# 12T_FULL_BRIDGE.net
KiCad netlist of a schematic drawn in EAGLE
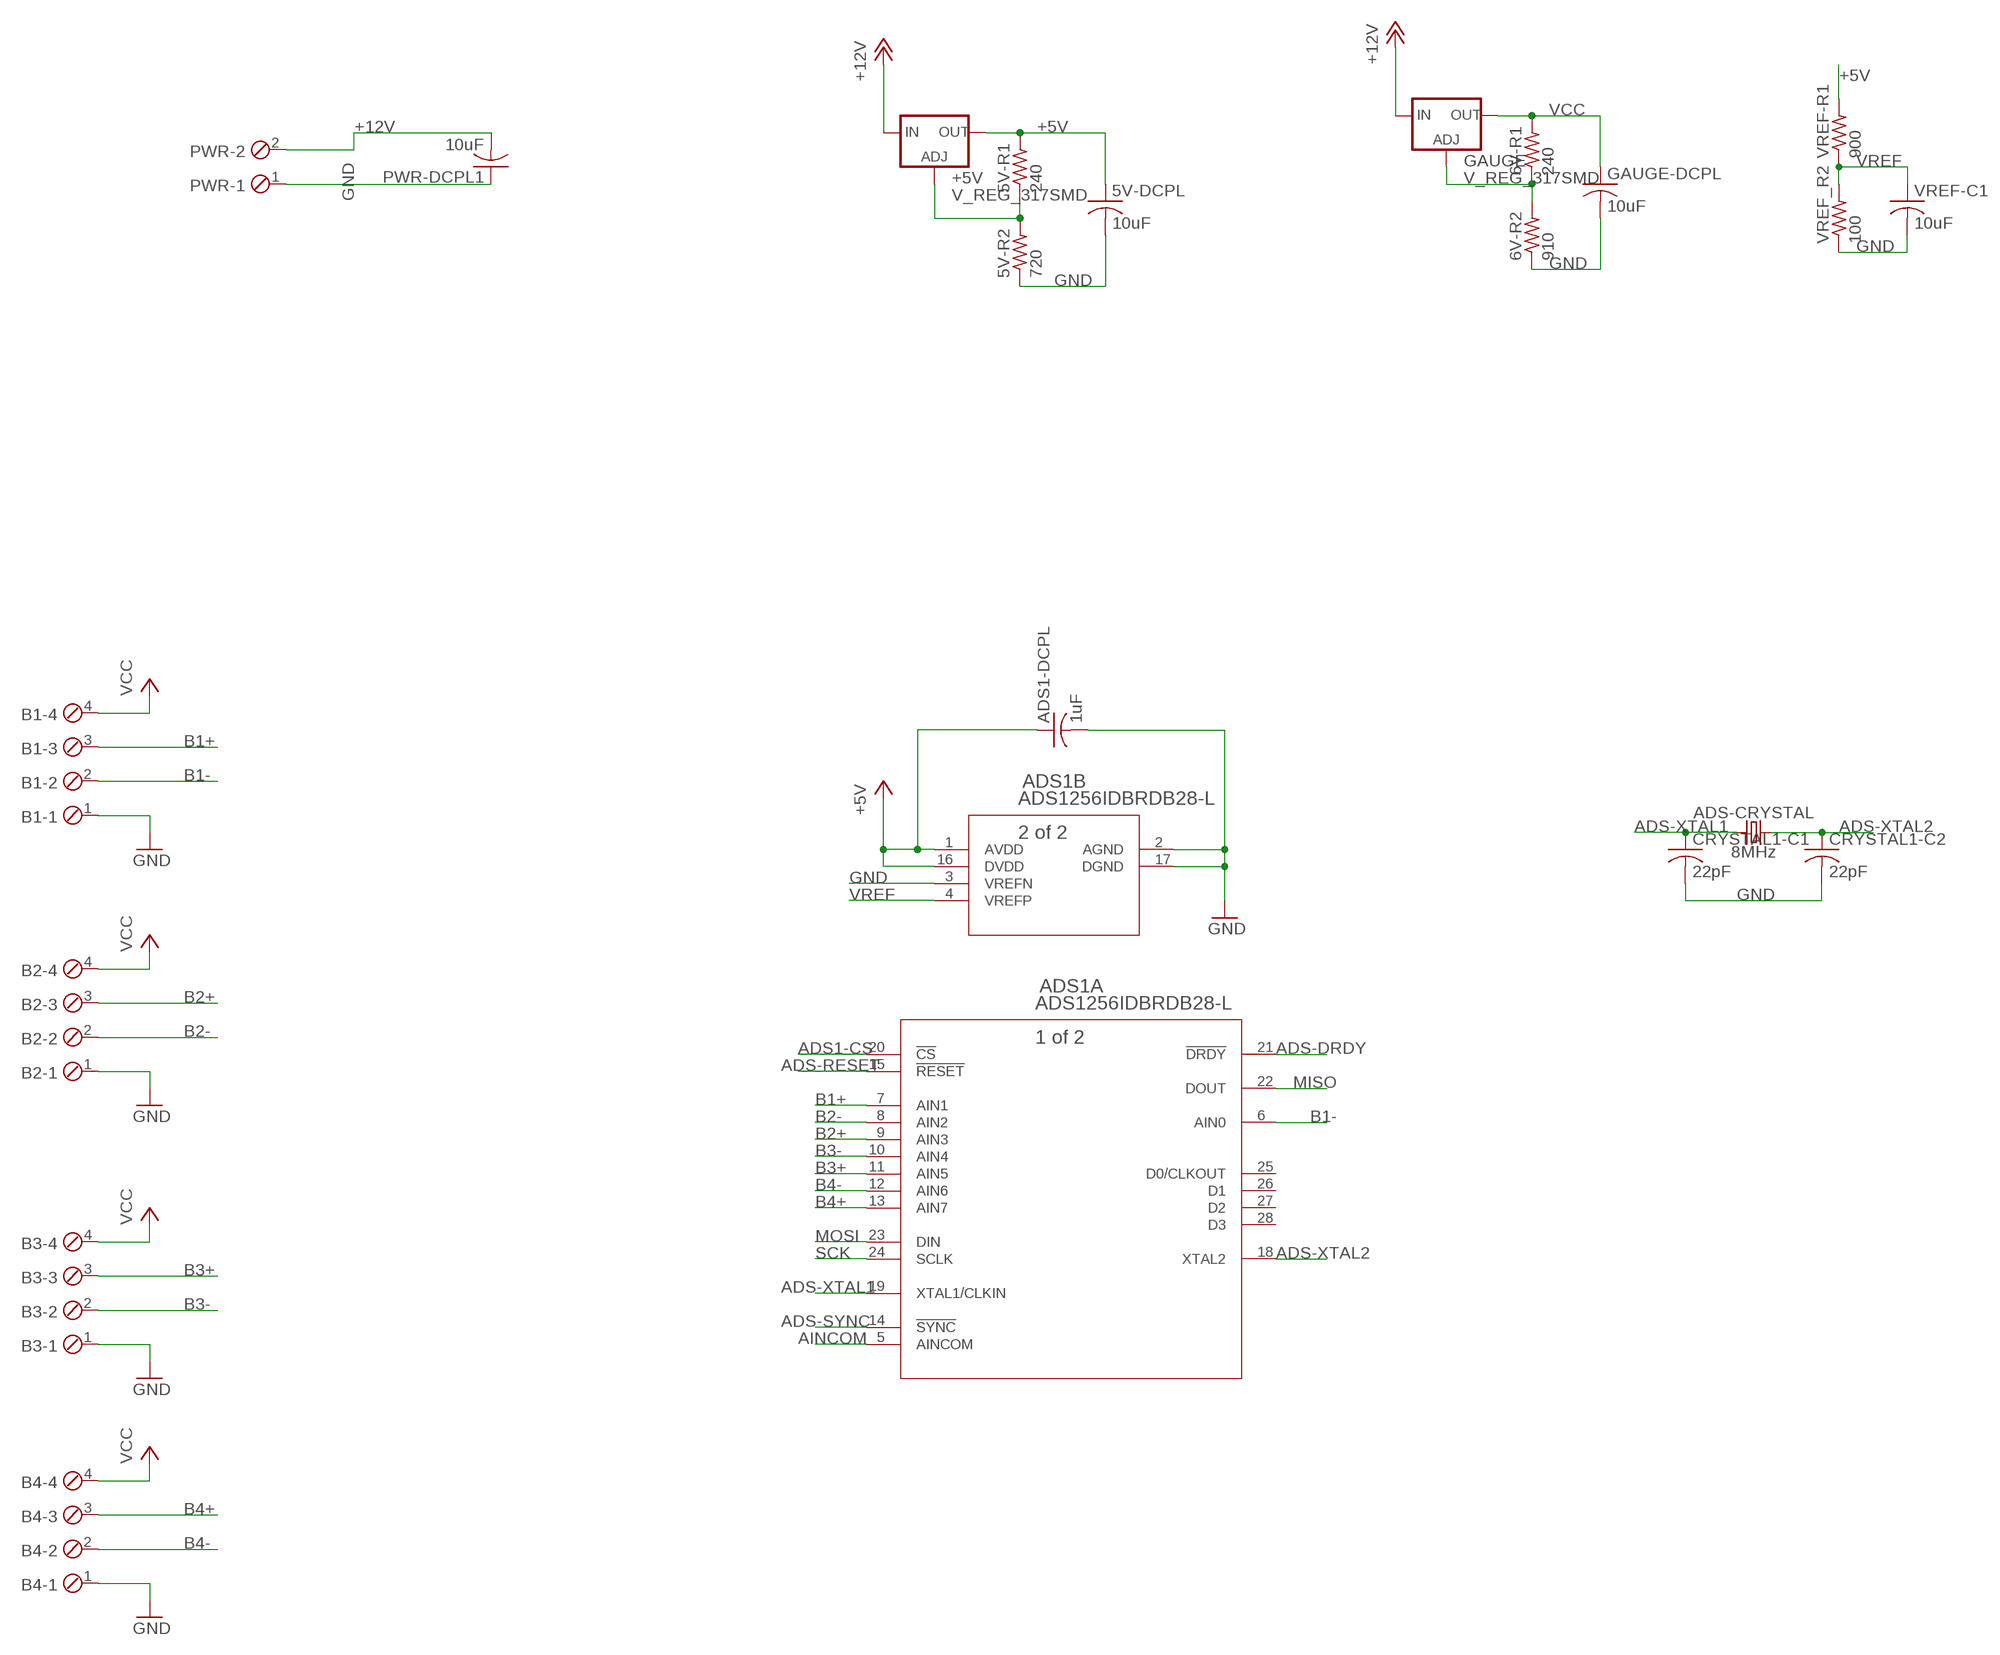
[diagram p0: schematic, sheet 1, part 1 of 2]
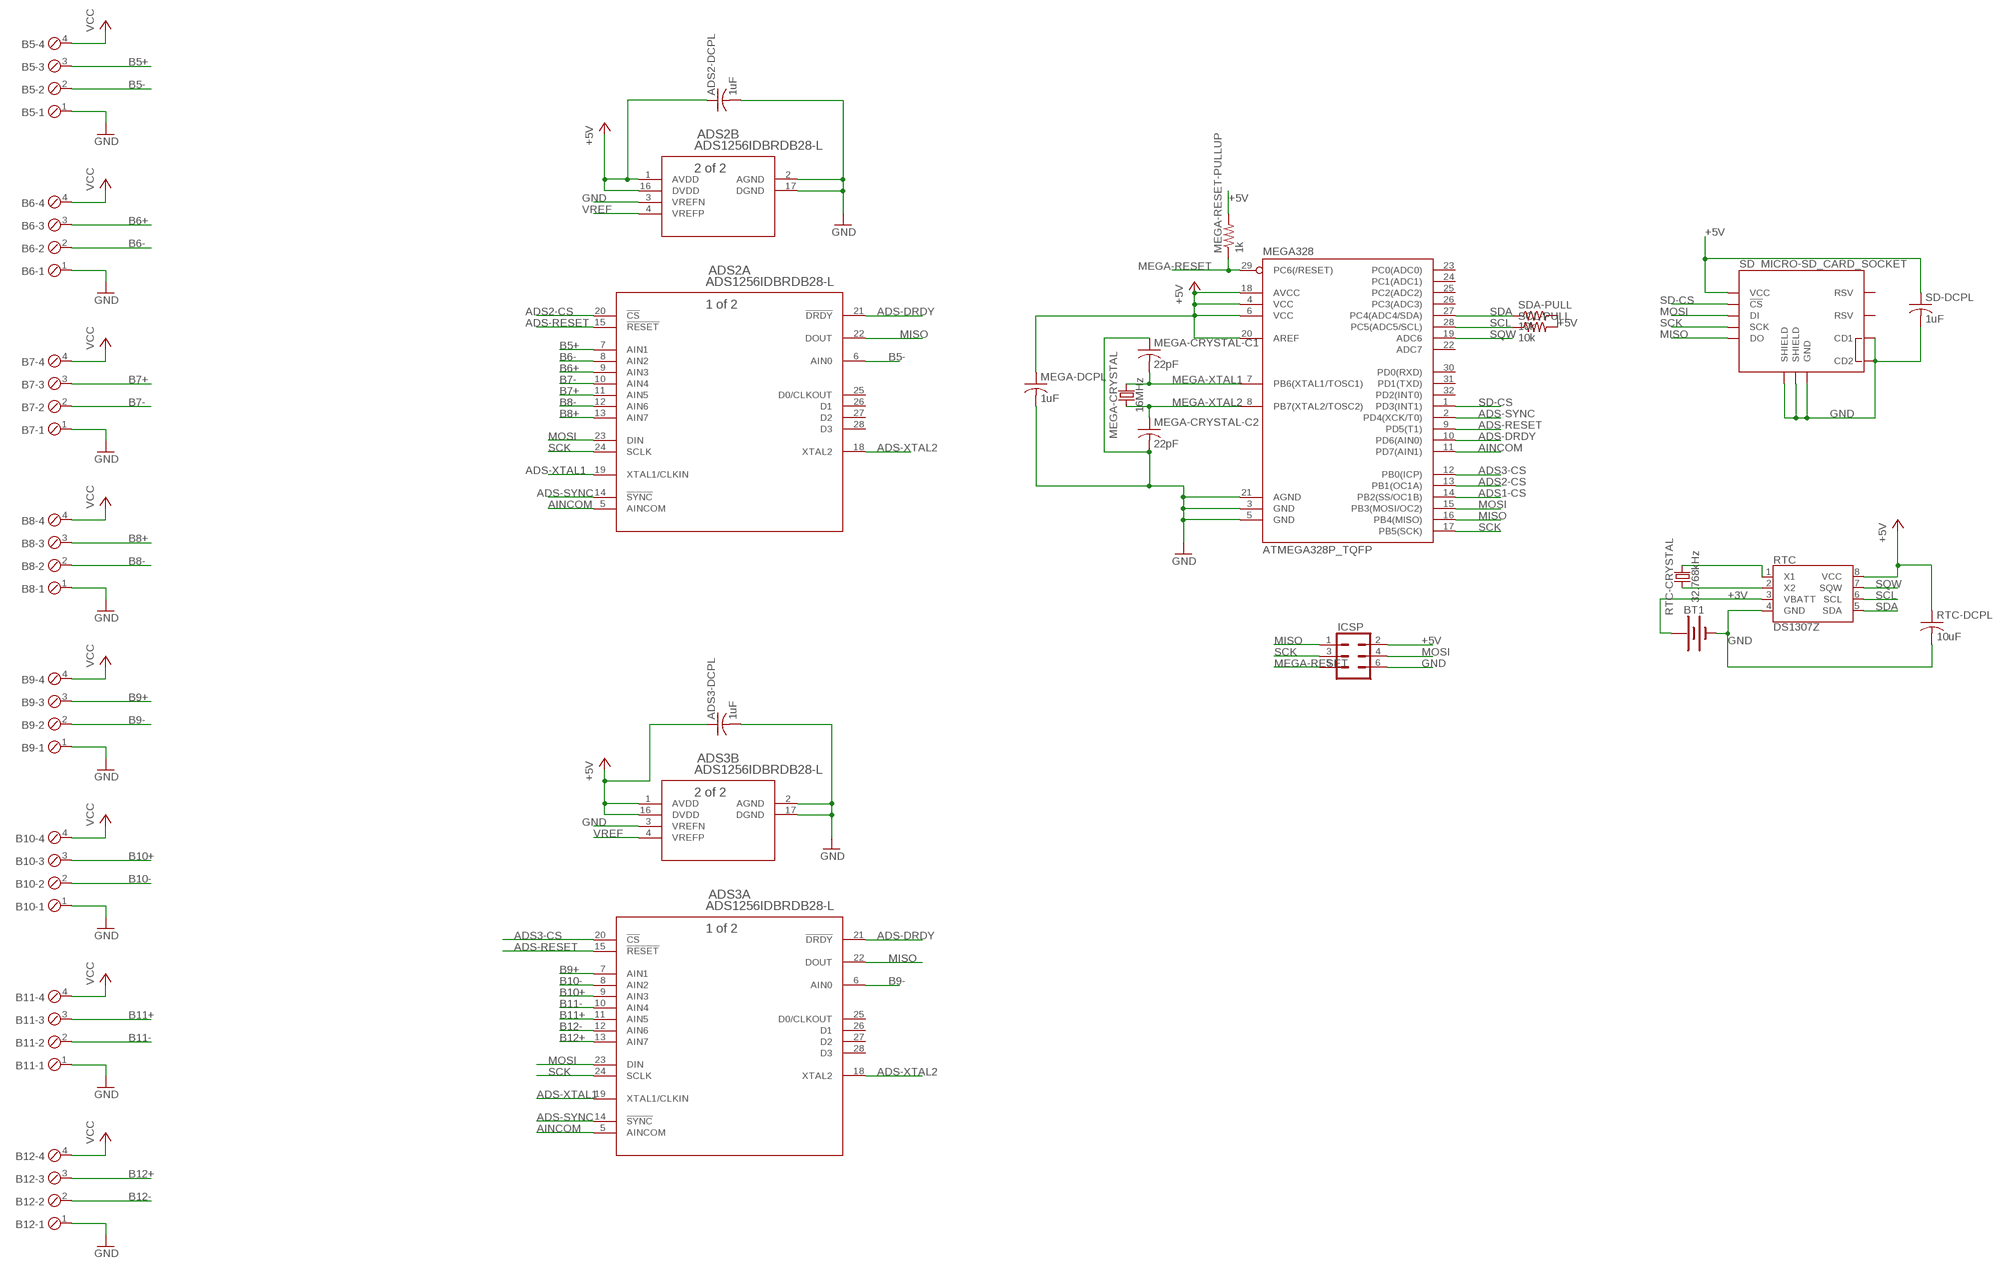
[diagram p1: schematic, sheet 1, part 2 of 2]

(export (version "E")
  (design (tool "Eeschema 10.0.6"))
  (components
    (comp (ref "+5V")
      (value "V_REG_317SMD")
      (footprint "eagle-import:SOT223")
      (libsource (lib "eagle-import") (part "V_REG_317SMD"))
    )
    (comp (ref "5V-DCPL")
      (value "10uF")
      (footprint "eagle-import:C1206")
      (libsource (lib "eagle-import") (part "C-USC1206"))
    )
    (comp (ref "5V-R1")
      (value "240")
      (footprint "eagle-import:R1206")
      (libsource (lib "eagle-import") (part "R-US_R1206"))
    )
    (comp (ref "5V-R2")
      (value "720")
      (footprint "eagle-import:R1206")
      (libsource (lib "eagle-import") (part "R-US_R1206"))
    )
    (comp (ref "6V-R1")
      (value "240")
      (footprint "eagle-import:R1206")
      (libsource (lib "eagle-import") (part "R-US_R1206"))
    )
    (comp (ref "6V-R2")
      (value "910")
      (footprint "eagle-import:R1206")
      (libsource (lib "eagle-import") (part "R-US_R1206"))
    )
    (comp (ref "ADS-CRYSTAL")
      (value "8MHz")
      (footprint "eagle-import:CRYSTAL-SMD-5X3.2-4PAD")
      (libsource (lib "eagle-import") (part "CRYSTAL-8MHZSMD-5X3.2"))
    )
    (comp (ref "ADS1")
      (value "ADS1256IDBRDB28-L")
      (footprint "eagle-import:DB28-L")
      (fields (field (name "MANUFACTURER_PART_NUMBER") "ADS1256IDBR"))
      (libsource (lib "eagle-import") (part "ADS1256IDBRDB28-L"))
    )
    (comp (ref "ADS1-DCPL")
      (value "1uF")
      (footprint "eagle-import:C1206K")
      (libsource (lib "eagle-import") (part "C-USC1206K"))
    )
    (comp (ref "ADS2")
      (value "ADS1256IDBRDB28-L")
      (footprint "eagle-import:DB28-L")
      (fields (field (name "MANUFACTURER_PART_NUMBER") "ADS1256IDBR"))
      (libsource (lib "eagle-import") (part "ADS1256IDBRDB28-L"))
    )
    (comp (ref "ADS2-DCPL")
      (value "1uF")
      (footprint "eagle-import:C1206K")
      (libsource (lib "eagle-import") (part "C-USC1206K"))
    )
    (comp (ref "ADS3")
      (value "ADS1256IDBRDB28-L")
      (footprint "eagle-import:DB28-L")
      (fields (field (name "MANUFACTURER_PART_NUMBER") "ADS1256IDBR"))
      (libsource (lib "eagle-import") (part "ADS1256IDBRDB28-L"))
    )
    (comp (ref "ADS3-DCPL")
      (value "1uF")
      (footprint "eagle-import:C1206K")
      (libsource (lib "eagle-import") (part "C-USC1206K"))
    )
    (comp (ref "B1")
      (value "MPT4")
      (footprint "eagle-import:4POL254")
      (libsource (lib "eagle-import") (part "MPT4"))
    )
    (comp (ref "B2")
      (value "MPT4")
      (footprint "eagle-import:4POL254")
      (libsource (lib "eagle-import") (part "MPT4"))
    )
    (comp (ref "B3")
      (value "MPT4")
      (footprint "eagle-import:4POL254")
      (libsource (lib "eagle-import") (part "MPT4"))
    )
    (comp (ref "B4")
      (value "MPT4")
      (footprint "eagle-import:4POL254")
      (libsource (lib "eagle-import") (part "MPT4"))
    )
    (comp (ref "B5")
      (value "MPT4")
      (footprint "eagle-import:4POL254")
      (libsource (lib "eagle-import") (part "MPT4"))
    )
    (comp (ref "B6")
      (value "MPT4")
      (footprint "eagle-import:4POL254")
      (libsource (lib "eagle-import") (part "MPT4"))
    )
    (comp (ref "B7")
      (value "MPT4")
      (footprint "eagle-import:4POL254")
      (libsource (lib "eagle-import") (part "MPT4"))
    )
    (comp (ref "B8")
      (value "MPT4")
      (footprint "eagle-import:4POL254")
      (libsource (lib "eagle-import") (part "MPT4"))
    )
    (comp (ref "B9")
      (value "MPT4")
      (footprint "eagle-import:4POL254")
      (libsource (lib "eagle-import") (part "MPT4"))
    )
    (comp (ref "B10")
      (value "MPT4")
      (footprint "eagle-import:4POL254")
      (libsource (lib "eagle-import") (part "MPT4"))
    )
    (comp (ref "B11")
      (value "MPT4")
      (footprint "eagle-import:4POL254")
      (libsource (lib "eagle-import") (part "MPT4"))
    )
    (comp (ref "B12")
      (value "MPT4")
      (footprint "eagle-import:4POL254")
      (libsource (lib "eagle-import") (part "MPT4"))
    )
    (comp (ref "BT1")
      (value "BATTERY-12MM_SMD")
      (footprint "eagle-import:BATTCON_12MM")
      (libsource (lib "eagle-import") (part "BATTERY-12MM_SMD"))
    )
    (comp (ref "CRYSTAL1-C1")
      (value "22pF")
      (footprint "eagle-import:C1206")
      (libsource (lib "eagle-import") (part "C-USC1206"))
    )
    (comp (ref "CRYSTAL1-C2")
      (value "22pF")
      (footprint "eagle-import:C1206")
      (libsource (lib "eagle-import") (part "C-USC1206"))
    )
    (comp (ref "GAUGE")
      (value "V_REG_317SMD")
      (footprint "eagle-import:SOT223")
      (libsource (lib "eagle-import") (part "V_REG_317SMD"))
    )
    (comp (ref "GAUGE-DCPL")
      (value "10uF")
      (footprint "eagle-import:C1206")
      (libsource (lib "eagle-import") (part "C-USC1206"))
    )
    (comp (ref "ICSP")
      (value "CONN_03X2FEMALE_SMD")
      (footprint "eagle-import:2X3_SMD")
      (libsource (lib "eagle-import") (part "CONN_03X2FEMALE_SMD"))
    )
    (comp (ref "MEGA-CRYSTAL")
      (value "16MHz")
      (footprint "eagle-import:CRYSTAL-SMD-5X3.2-4PAD")
      (libsource (lib "eagle-import") (part "CRYSTAL-16MHZSMD-5X3.2"))
    )
    (comp (ref "MEGA-CRYSTAL-C1")
      (value "22pF")
      (footprint "eagle-import:C1206K")
      (libsource (lib "eagle-import") (part "C-USC1206K"))
    )
    (comp (ref "MEGA-CRYSTAL-C2")
      (value "22pF")
      (footprint "eagle-import:C1206K")
      (libsource (lib "eagle-import") (part "C-USC1206K"))
    )
    (comp (ref "MEGA-DCPL")
      (value "1uF")
      (footprint "eagle-import:C1206K")
      (libsource (lib "eagle-import") (part "C-USC1206K"))
    )
    (comp (ref "MEGA-RESET-PULLUP")
      (value "1k")
      (footprint "eagle-import:R1206")
      (libsource (lib "eagle-import") (part "R-US_R1206"))
    )
    (comp (ref "MEGA328")
      (value "ATMEGA328P_TQFP")
      (footprint "eagle-import:TQFP32-08")
      (libsource (lib "eagle-import") (part "ATMEGA328P_TQFP"))
    )
    (comp (ref "PWR")
      (value "MPT2")
      (footprint "eagle-import:2POL254")
      (libsource (lib "eagle-import") (part "MPT2"))
    )
    (comp (ref "PWR-DCPL1")
      (value "10uF")
      (footprint "eagle-import:C1206")
      (libsource (lib "eagle-import") (part "C-USC1206"))
    )
    (comp (ref "RTC")
      (value "DS1307Z")
      (footprint "eagle-import:SO08-0.15")
      (libsource (lib "eagle-import") (part "DS1307Z"))
    )
    (comp (ref "RTC-CRYSTAL")
      (value "32.768kHz")
      (footprint "eagle-import:CRYSTAL-SMD-3.2X1.5MM")
      (libsource (lib "eagle-import") (part "CRYSTAL-32.768KHZSMD-3.2X1.5"))
    )
    (comp (ref "RTC-DCPL")
      (value "10uF")
      (footprint "eagle-import:C1206")
      (libsource (lib "eagle-import") (part "C-USC1206"))
    )
    (comp (ref "SCL-PULL")
      (value "10k")
      (footprint "eagle-import:R1206")
      (libsource (lib "eagle-import") (part "resistor_348_R-US_R1206"))
    )
    (comp (ref "SD")
      (value "MICRO-SD_CARD_SOCKET")
      (footprint "eagle-import:MICRO-SD-SOCKET")
      (libsource (lib "eagle-import") (part "MICRO-SD_CARD_SOCKET"))
    )
    (comp (ref "SD-DCPL")
      (value "1uF")
      (footprint "eagle-import:C1206K")
      (libsource (lib "eagle-import") (part "resistor_348_C-USC1206K"))
    )
    (comp (ref "SDA-PULL")
      (value "10k")
      (footprint "eagle-import:R1206")
      (libsource (lib "eagle-import") (part "resistor_348_R-US_R1206"))
    )
    (comp (ref "VREF-C1")
      (value "10uF")
      (footprint "eagle-import:C1206")
      (libsource (lib "eagle-import") (part "C-USC1206"))
    )
    (comp (ref "VREF-R1")
      (value "900")
      (footprint "eagle-import:R1206")
      (libsource (lib "eagle-import") (part "R-US_R1206"))
    )
    (comp (ref "VREF_R2")
      (value "100")
      (footprint "eagle-import:R1206")
      (libsource (lib "eagle-import") (part "R-US_R1206"))
    )
  )
  (nets
    (net (code "1") (name "+5V") (class "Default")
      (node (ref "+5V") (pin "2") (pinfunction "OUT_2") (pintype "output"))
      (node (ref "5V-DCPL") (pin "1") (pinfunction "1_1") (pintype "passive"))
      (node (ref "5V-R1") (pin "2") (pinfunction "2_2") (pintype "passive"))
      (node (ref "ADS1") (pin "1") (pinfunction "AVDD_1") (pintype "passive"))
      (node (ref "ADS1") (pin "16") (pinfunction "DVDD_16") (pintype "power_in"))
      (node (ref "ADS1-DCPL") (pin "1") (pinfunction "1_1") (pintype "passive"))
      (node (ref "ADS2") (pin "1") (pinfunction "AVDD_1") (pintype "passive"))
      (node (ref "ADS2") (pin "16") (pinfunction "DVDD_16") (pintype "power_in"))
      (node (ref "ADS2-DCPL") (pin "1") (pinfunction "1_1") (pintype "passive"))
      (node (ref "ADS3") (pin "1") (pinfunction "AVDD_1") (pintype "passive"))
      (node (ref "ADS3") (pin "16") (pinfunction "DVDD_16") (pintype "power_in"))
      (node (ref "ADS3-DCPL") (pin "1") (pinfunction "1_1") (pintype "passive"))
      (node (ref "ICSP") (pin "2") (pinfunction "2_2") (pintype "bidirectional"))
      (node (ref "MEGA-DCPL") (pin "1") (pinfunction "1_1") (pintype "passive"))
      (node (ref "MEGA-RESET-PULLUP") (pin "2") (pinfunction "2_2") (pintype "passive"))
      (node (ref "MEGA328") (pin "18") (pinfunction "AVCC_18") (pintype "bidirectional"))
      (node (ref "MEGA328") (pin "20") (pinfunction "AREF_20") (pintype "bidirectional"))
      (node (ref "MEGA328") (pin "4") (pinfunction "VCC_4") (pintype "bidirectional"))
      (node (ref "MEGA328") (pin "6") (pinfunction "VCC_6") (pintype "bidirectional"))
      (node (ref "RTC") (pin "8") (pinfunction "VCC_8") (pintype "bidirectional"))
      (node (ref "RTC-DCPL") (pin "1") (pinfunction "1_1") (pintype "passive"))
      (node (ref "SCL-PULL") (pin "2") (pinfunction "2_2") (pintype "passive"))
      (node (ref "SD") (pin "VCC") (pinfunction "VCC_VCC") (pintype "bidirectional"))
      (node (ref "SD-DCPL") (pin "1") (pinfunction "1_1") (pintype "passive"))
      (node (ref "SDA-PULL") (pin "2") (pinfunction "2_2") (pintype "passive"))
      (node (ref "VREF-R1") (pin "2") (pinfunction "2_2") (pintype "passive"))
    )
    (net (code "2") (name "+12V") (class "Default")
      (node (ref "+5V") (pin "3") (pinfunction "IN_3") (pintype "input"))
      (node (ref "GAUGE") (pin "3") (pinfunction "IN_3") (pintype "input"))
      (node (ref "PWR") (pin "2") (pinfunction "1_2") (pintype "passive"))
      (node (ref "PWR-DCPL1") (pin "2") (pinfunction "2_2") (pintype "passive"))
    )
    (net (code "3") (name "/+3V") (class "Default")
      (node (ref "BT1") (pin "PWR@1") (pinfunction "+_PWR@1") (pintype "power_in"))
      (node (ref "RTC") (pin "3") (pinfunction "VBATT_3") (pintype "bidirectional"))
    )
    (net (code "4") (name "/ADS-DRDY") (class "Default")
      (node (ref "ADS1") (pin "21") (pinfunction "~{DRDY}_21") (pintype "output"))
      (node (ref "ADS2") (pin "21") (pinfunction "~{DRDY}_21") (pintype "output"))
      (node (ref "ADS3") (pin "21") (pinfunction "~{DRDY}_21") (pintype "output"))
      (node (ref "MEGA328") (pin "10") (pinfunction "PD6(AIN0)_10") (pintype "bidirectional"))
    )
    (net (code "5") (name "/ADS-RESET") (class "Default")
      (node (ref "ADS1") (pin "15") (pinfunction "~{RESET}_15") (pintype "input"))
      (node (ref "ADS2") (pin "15") (pinfunction "~{RESET}_15") (pintype "input"))
      (node (ref "ADS3") (pin "15") (pinfunction "~{RESET}_15") (pintype "input"))
      (node (ref "MEGA328") (pin "9") (pinfunction "PD5(T1)_9") (pintype "bidirectional"))
    )
    (net (code "6") (name "/ADS-SYNC") (class "Default")
      (node (ref "ADS1") (pin "14") (pinfunction "~{SYNC}_14") (pintype "passive"))
      (node (ref "ADS2") (pin "14") (pinfunction "~{SYNC}_14") (pintype "passive"))
      (node (ref "ADS3") (pin "14") (pinfunction "~{SYNC}_14") (pintype "passive"))
      (node (ref "MEGA328") (pin "2") (pinfunction "PD4(XCK/T0)_2") (pintype "bidirectional"))
    )
    (net (code "7") (name "/ADS-XTAL1") (class "Default")
      (node (ref "ADS-CRYSTAL") (pin "1") (pinfunction "1_1") (pintype "passive"))
      (node (ref "ADS1") (pin "19") (pinfunction "XTAL1/CLKIN_19") (pintype "input"))
      (node (ref "ADS2") (pin "19") (pinfunction "XTAL1/CLKIN_19") (pintype "input"))
      (node (ref "ADS3") (pin "19") (pinfunction "XTAL1/CLKIN_19") (pintype "input"))
      (node (ref "CRYSTAL1-C1") (pin "1") (pinfunction "1_1") (pintype "passive"))
    )
    (net (code "8") (name "/ADS-XTAL2") (class "Default")
      (node (ref "ADS-CRYSTAL") (pin "3") (pinfunction "2_3") (pintype "passive"))
      (node (ref "ADS1") (pin "18") (pinfunction "XTAL2_18") (pintype "passive"))
      (node (ref "ADS2") (pin "18") (pinfunction "XTAL2_18") (pintype "passive"))
      (node (ref "ADS3") (pin "18") (pinfunction "XTAL2_18") (pintype "passive"))
      (node (ref "CRYSTAL1-C2") (pin "1") (pinfunction "1_1") (pintype "passive"))
    )
    (net (code "9") (name "/ADS1-CS") (class "Default")
      (node (ref "ADS1") (pin "20") (pinfunction "~{CS}_20") (pintype "input"))
      (node (ref "MEGA328") (pin "14") (pinfunction "PB2(SS/OC1B)_14") (pintype "bidirectional"))
    )
    (net (code "10") (name "/ADS2-CS") (class "Default")
      (node (ref "ADS2") (pin "20") (pinfunction "~{CS}_20") (pintype "input"))
      (node (ref "MEGA328") (pin "13") (pinfunction "PB1(OC1A)_13") (pintype "bidirectional"))
    )
    (net (code "11") (name "/ADS3-CS") (class "Default")
      (node (ref "ADS3") (pin "20") (pinfunction "~{CS}_20") (pintype "input"))
      (node (ref "MEGA328") (pin "12") (pinfunction "PB0(ICP)_12") (pintype "bidirectional"))
    )
    (net (code "12") (name "/AINCOM") (class "Default")
      (node (ref "ADS1") (pin "5") (pinfunction "AINCOM_5") (pintype "passive"))
      (node (ref "ADS2") (pin "5") (pinfunction "AINCOM_5") (pintype "passive"))
      (node (ref "ADS3") (pin "5") (pinfunction "AINCOM_5") (pintype "passive"))
      (node (ref "MEGA328") (pin "11") (pinfunction "PD7(AIN1)_11") (pintype "bidirectional"))
    )
    (net (code "13") (name "/B1+") (class "Default")
      (node (ref "ADS1") (pin "7") (pinfunction "AIN1_7") (pintype "passive"))
      (node (ref "B1") (pin "3") (pinfunction "1_3") (pintype "passive"))
    )
    (net (code "14") (name "/B1-") (class "Default")
      (node (ref "ADS1") (pin "6") (pinfunction "AIN0_6") (pintype "passive"))
      (node (ref "B1") (pin "2") (pinfunction "1_2") (pintype "passive"))
    )
    (net (code "15") (name "/B2+") (class "Default")
      (node (ref "ADS1") (pin "9") (pinfunction "AIN3_9") (pintype "passive"))
      (node (ref "B2") (pin "3") (pinfunction "1_3") (pintype "passive"))
    )
    (net (code "16") (name "/B2-") (class "Default")
      (node (ref "ADS1") (pin "8") (pinfunction "AIN2_8") (pintype "passive"))
      (node (ref "B2") (pin "2") (pinfunction "1_2") (pintype "passive"))
    )
    (net (code "17") (name "/B3+") (class "Default")
      (node (ref "ADS1") (pin "11") (pinfunction "AIN5_11") (pintype "passive"))
      (node (ref "B3") (pin "3") (pinfunction "1_3") (pintype "passive"))
    )
    (net (code "18") (name "/B3-") (class "Default")
      (node (ref "ADS1") (pin "10") (pinfunction "AIN4_10") (pintype "passive"))
      (node (ref "B3") (pin "2") (pinfunction "1_2") (pintype "passive"))
    )
    (net (code "19") (name "/B4+") (class "Default")
      (node (ref "ADS1") (pin "13") (pinfunction "AIN7_13") (pintype "passive"))
      (node (ref "B4") (pin "3") (pinfunction "1_3") (pintype "passive"))
    )
    (net (code "20") (name "/B4-") (class "Default")
      (node (ref "ADS1") (pin "12") (pinfunction "AIN6_12") (pintype "passive"))
      (node (ref "B4") (pin "2") (pinfunction "1_2") (pintype "passive"))
    )
    (net (code "21") (name "/B5+") (class "Default")
      (node (ref "ADS2") (pin "7") (pinfunction "AIN1_7") (pintype "passive"))
      (node (ref "B5") (pin "3") (pinfunction "1_3") (pintype "passive"))
    )
    (net (code "22") (name "/B5-") (class "Default")
      (node (ref "ADS2") (pin "6") (pinfunction "AIN0_6") (pintype "passive"))
      (node (ref "B5") (pin "2") (pinfunction "1_2") (pintype "passive"))
    )
    (net (code "23") (name "/B6+") (class "Default")
      (node (ref "ADS2") (pin "9") (pinfunction "AIN3_9") (pintype "passive"))
      (node (ref "B6") (pin "3") (pinfunction "1_3") (pintype "passive"))
    )
    (net (code "24") (name "/B6-") (class "Default")
      (node (ref "ADS2") (pin "8") (pinfunction "AIN2_8") (pintype "passive"))
      (node (ref "B6") (pin "2") (pinfunction "1_2") (pintype "passive"))
    )
    (net (code "25") (name "/B7+") (class "Default")
      (node (ref "ADS2") (pin "11") (pinfunction "AIN5_11") (pintype "passive"))
      (node (ref "B7") (pin "3") (pinfunction "1_3") (pintype "passive"))
    )
    (net (code "26") (name "/B7-") (class "Default")
      (node (ref "ADS2") (pin "10") (pinfunction "AIN4_10") (pintype "passive"))
      (node (ref "B7") (pin "2") (pinfunction "1_2") (pintype "passive"))
    )
    (net (code "27") (name "/B8+") (class "Default")
      (node (ref "ADS2") (pin "13") (pinfunction "AIN7_13") (pintype "passive"))
      (node (ref "B8") (pin "3") (pinfunction "1_3") (pintype "passive"))
    )
    (net (code "28") (name "/B8-") (class "Default")
      (node (ref "ADS2") (pin "12") (pinfunction "AIN6_12") (pintype "passive"))
      (node (ref "B8") (pin "2") (pinfunction "1_2") (pintype "passive"))
    )
    (net (code "29") (name "/B9+") (class "Default")
      (node (ref "ADS3") (pin "7") (pinfunction "AIN1_7") (pintype "passive"))
      (node (ref "B9") (pin "3") (pinfunction "1_3") (pintype "passive"))
    )
    (net (code "30") (name "/B9-") (class "Default")
      (node (ref "ADS3") (pin "6") (pinfunction "AIN0_6") (pintype "passive"))
      (node (ref "B9") (pin "2") (pinfunction "1_2") (pintype "passive"))
    )
    (net (code "31") (name "/B10+") (class "Default")
      (node (ref "ADS3") (pin "9") (pinfunction "AIN3_9") (pintype "passive"))
      (node (ref "B10") (pin "3") (pinfunction "1_3") (pintype "passive"))
    )
    (net (code "32") (name "/B10-") (class "Default")
      (node (ref "ADS3") (pin "8") (pinfunction "AIN2_8") (pintype "passive"))
      (node (ref "B10") (pin "2") (pinfunction "1_2") (pintype "passive"))
    )
    (net (code "33") (name "/B11+") (class "Default")
      (node (ref "ADS3") (pin "11") (pinfunction "AIN5_11") (pintype "passive"))
      (node (ref "B11") (pin "3") (pinfunction "1_3") (pintype "passive"))
    )
    (net (code "34") (name "/B11-") (class "Default")
      (node (ref "ADS3") (pin "10") (pinfunction "AIN4_10") (pintype "passive"))
      (node (ref "B11") (pin "2") (pinfunction "1_2") (pintype "passive"))
    )
    (net (code "35") (name "/B12+") (class "Default")
      (node (ref "ADS3") (pin "13") (pinfunction "AIN7_13") (pintype "passive"))
      (node (ref "B12") (pin "3") (pinfunction "1_3") (pintype "passive"))
    )
    (net (code "36") (name "/B12-") (class "Default")
      (node (ref "ADS3") (pin "12") (pinfunction "AIN6_12") (pintype "passive"))
      (node (ref "B12") (pin "2") (pinfunction "1_2") (pintype "passive"))
    )
    (net (code "37") (name "/MEGA-RESET") (class "Default")
      (node (ref "ICSP") (pin "5") (pinfunction "5_5") (pintype "bidirectional"))
      (node (ref "MEGA-RESET-PULLUP") (pin "1") (pinfunction "1_1") (pintype "passive"))
      (node (ref "MEGA328") (pin "29") (pinfunction "PC6(/RESET)_29") (pintype "bidirectional"))
    )
    (net (code "38") (name "/MEGA-XTAL1") (class "Default")
      (node (ref "MEGA-CRYSTAL") (pin "3") (pinfunction "2_3") (pintype "passive"))
      (node (ref "MEGA-CRYSTAL-C1") (pin "2") (pinfunction "2_2") (pintype "passive"))
      (node (ref "MEGA328") (pin "7") (pinfunction "PB6(XTAL1/TOSC1)_7") (pintype "bidirectional"))
    )
    (net (code "39") (name "/MEGA-XTAL2") (class "Default")
      (node (ref "MEGA-CRYSTAL") (pin "1") (pinfunction "1_1") (pintype "passive"))
      (node (ref "MEGA-CRYSTAL-C2") (pin "1") (pinfunction "1_1") (pintype "passive"))
      (node (ref "MEGA328") (pin "8") (pinfunction "PB7(XTAL2/TOSC2)_8") (pintype "bidirectional"))
    )
    (net (code "40") (name "/MISO") (class "Default")
      (node (ref "ADS1") (pin "22") (pinfunction "DOUT_22") (pintype "output"))
      (node (ref "ADS2") (pin "22") (pinfunction "DOUT_22") (pintype "output"))
      (node (ref "ADS3") (pin "22") (pinfunction "DOUT_22") (pintype "output"))
      (node (ref "ICSP") (pin "1") (pinfunction "1_1") (pintype "bidirectional"))
      (node (ref "MEGA328") (pin "16") (pinfunction "PB4(MISO)_16") (pintype "bidirectional"))
      (node (ref "SD") (pin "DO") (pinfunction "DO_DO") (pintype "bidirectional"))
    )
    (net (code "41") (name "/MOSI") (class "Default")
      (node (ref "ADS1") (pin "23") (pinfunction "DIN_23") (pintype "input"))
      (node (ref "ADS2") (pin "23") (pinfunction "DIN_23") (pintype "input"))
      (node (ref "ADS3") (pin "23") (pinfunction "DIN_23") (pintype "input"))
      (node (ref "ICSP") (pin "4") (pinfunction "4_4") (pintype "bidirectional"))
      (node (ref "MEGA328") (pin "15") (pinfunction "PB3(MOSI/OC2)_15") (pintype "bidirectional"))
      (node (ref "SD") (pin "DI") (pinfunction "DI_DI") (pintype "bidirectional"))
    )
    (net (code "42") (name "/SCK") (class "Default")
      (node (ref "ADS1") (pin "24") (pinfunction "SCLK_24") (pintype "input"))
      (node (ref "ADS2") (pin "24") (pinfunction "SCLK_24") (pintype "input"))
      (node (ref "ADS3") (pin "24") (pinfunction "SCLK_24") (pintype "input"))
      (node (ref "ICSP") (pin "3") (pinfunction "3_3") (pintype "bidirectional"))
      (node (ref "MEGA328") (pin "17") (pinfunction "PB5(SCK)_17") (pintype "bidirectional"))
      (node (ref "SD") (pin "SCLK") (pinfunction "SCK_SCLK") (pintype "bidirectional"))
    )
    (net (code "43") (name "/SCL") (class "Default")
      (node (ref "MEGA328") (pin "28") (pinfunction "PC5(ADC5/SCL)_28") (pintype "bidirectional"))
      (node (ref "RTC") (pin "6") (pinfunction "SCL_6") (pintype "bidirectional"))
      (node (ref "SCL-PULL") (pin "1") (pinfunction "1_1") (pintype "passive"))
    )
    (net (code "44") (name "/SD-CS") (class "Default")
      (node (ref "MEGA328") (pin "1") (pinfunction "PD3(INT1)_1") (pintype "bidirectional"))
      (node (ref "SD") (pin "CS") (pinfunction "~{CS}_CS") (pintype "bidirectional"))
    )
    (net (code "45") (name "/SDA") (class "Default")
      (node (ref "MEGA328") (pin "27") (pinfunction "PC4(ADC4/SDA)_27") (pintype "bidirectional"))
      (node (ref "RTC") (pin "5") (pinfunction "SDA_5") (pintype "bidirectional"))
      (node (ref "SDA-PULL") (pin "1") (pinfunction "1_1") (pintype "passive"))
    )
    (net (code "46") (name "/SQW") (class "Default")
      (node (ref "MEGA328") (pin "19") (pinfunction "ADC6_19") (pintype "bidirectional"))
      (node (ref "RTC") (pin "7") (pinfunction "SQW_7") (pintype "bidirectional"))
    )
    (net (code "47") (name "/VREF") (class "Default")
      (node (ref "ADS1") (pin "4") (pinfunction "VREFP_4") (pintype "passive"))
      (node (ref "ADS2") (pin "4") (pinfunction "VREFP_4") (pintype "passive"))
      (node (ref "ADS3") (pin "4") (pinfunction "VREFP_4") (pintype "passive"))
      (node (ref "VREF-C1") (pin "1") (pinfunction "1_1") (pintype "passive"))
      (node (ref "VREF-R1") (pin "1") (pinfunction "1_1") (pintype "passive"))
      (node (ref "VREF_R2") (pin "2") (pinfunction "2_2") (pintype "passive"))
    )
    (net (code "48") (name "GND") (class "Default")
      (node (ref "5V-DCPL") (pin "2") (pinfunction "2_2") (pintype "passive"))
      (node (ref "5V-R2") (pin "1") (pinfunction "1_1") (pintype "passive"))
      (node (ref "6V-R2") (pin "1") (pinfunction "1_1") (pintype "passive"))
      (node (ref "ADS1") (pin "17") (pinfunction "DGND_17") (pintype "power_in"))
      (node (ref "ADS1") (pin "2") (pinfunction "AGND_2") (pintype "passive"))
      (node (ref "ADS1") (pin "3") (pinfunction "VREFN_3") (pintype "passive"))
      (node (ref "ADS1-DCPL") (pin "2") (pinfunction "2_2") (pintype "passive"))
      (node (ref "ADS2") (pin "17") (pinfunction "DGND_17") (pintype "power_in"))
      (node (ref "ADS2") (pin "2") (pinfunction "AGND_2") (pintype "passive"))
      (node (ref "ADS2") (pin "3") (pinfunction "VREFN_3") (pintype "passive"))
      (node (ref "ADS2-DCPL") (pin "2") (pinfunction "2_2") (pintype "passive"))
      (node (ref "ADS3") (pin "17") (pinfunction "DGND_17") (pintype "power_in"))
      (node (ref "ADS3") (pin "2") (pinfunction "AGND_2") (pintype "passive"))
      (node (ref "ADS3") (pin "3") (pinfunction "VREFN_3") (pintype "passive"))
      (node (ref "ADS3-DCPL") (pin "2") (pinfunction "2_2") (pintype "passive"))
      (node (ref "B1") (pin "1") (pinfunction "1_1") (pintype "passive"))
      (node (ref "B10") (pin "1") (pinfunction "1_1") (pintype "passive"))
      (node (ref "B11") (pin "1") (pinfunction "1_1") (pintype "passive"))
      (node (ref "B12") (pin "1") (pinfunction "1_1") (pintype "passive"))
      (node (ref "B2") (pin "1") (pinfunction "1_1") (pintype "passive"))
      (node (ref "B3") (pin "1") (pinfunction "1_1") (pintype "passive"))
      (node (ref "B4") (pin "1") (pinfunction "1_1") (pintype "passive"))
      (node (ref "B5") (pin "1") (pinfunction "1_1") (pintype "passive"))
      (node (ref "B6") (pin "1") (pinfunction "1_1") (pintype "passive"))
      (node (ref "B7") (pin "1") (pinfunction "1_1") (pintype "passive"))
      (node (ref "B8") (pin "1") (pinfunction "1_1") (pintype "passive"))
      (node (ref "B9") (pin "1") (pinfunction "1_1") (pintype "passive"))
      (node (ref "BT1") (pin "GND") (pinfunction "-_GND") (pintype "power_in"))
      (node (ref "CRYSTAL1-C1") (pin "2") (pinfunction "2_2") (pintype "passive"))
      (node (ref "CRYSTAL1-C2") (pin "2") (pinfunction "2_2") (pintype "passive"))
      (node (ref "GAUGE-DCPL") (pin "2") (pinfunction "2_2") (pintype "passive"))
      (node (ref "ICSP") (pin "6") (pinfunction "6_6") (pintype "bidirectional"))
      (node (ref "MEGA-CRYSTAL-C1") (pin "1") (pinfunction "1_1") (pintype "passive"))
      (node (ref "MEGA-CRYSTAL-C2") (pin "2") (pinfunction "2_2") (pintype "passive"))
      (node (ref "MEGA-DCPL") (pin "2") (pinfunction "2_2") (pintype "passive"))
      (node (ref "MEGA328") (pin "21") (pinfunction "AGND_21") (pintype "bidirectional"))
      (node (ref "MEGA328") (pin "3") (pinfunction "GND_3") (pintype "bidirectional"))
      (node (ref "MEGA328") (pin "5") (pinfunction "GND_5") (pintype "bidirectional"))
      (node (ref "PWR") (pin "1") (pinfunction "1_1") (pintype "passive"))
      (node (ref "PWR-DCPL1") (pin "1") (pinfunction "1_1") (pintype "passive"))
      (node (ref "RTC") (pin "4") (pinfunction "GND_4") (pintype "bidirectional"))
      (node (ref "RTC-DCPL") (pin "2") (pinfunction "2_2") (pintype "passive"))
      (node (ref "SD") (pin "CD1") (pinfunction "CD1_CD1") (pintype "bidirectional"))
      (node (ref "SD") (pin "CD2") (pinfunction "CD2_CD2") (pintype "bidirectional"))
      (node (ref "SD") (pin "GND") (pinfunction "GND_GND") (pintype "bidirectional"))
      (node (ref "SD") (pin "GND1") (pinfunction "SHIELD_GND1") (pintype "bidirectional"))
      (node (ref "SD") (pin "GND3") (pinfunction "SHIELD_GND3") (pintype "bidirectional"))
      (node (ref "SD-DCPL") (pin "2") (pinfunction "2_2") (pintype "passive"))
      (node (ref "VREF-C1") (pin "2") (pinfunction "2_2") (pintype "passive"))
      (node (ref "VREF_R2") (pin "1") (pinfunction "1_1") (pintype "passive"))
    )
    (net (code "49") (name "Net-(+5V-ADJ)") (class "Default")
      (node (ref "+5V") (pin "1") (pinfunction "ADJ_1") (pintype "input"))
      (node (ref "5V-R1") (pin "1") (pinfunction "1_1") (pintype "passive"))
      (node (ref "5V-R2") (pin "2") (pinfunction "2_2") (pintype "passive"))
    )
    (net (code "50") (name "Net-(GAUGE-ADJ)") (class "Default")
      (node (ref "6V-R1") (pin "1") (pinfunction "1_1") (pintype "passive"))
      (node (ref "6V-R2") (pin "2") (pinfunction "2_2") (pintype "passive"))
      (node (ref "GAUGE") (pin "1") (pinfunction "ADJ_1") (pintype "input"))
    )
    (net (code "51") (name "Net-(RTC-CRYSTAL-1)") (class "Default")
      (node (ref "RTC") (pin "2") (pinfunction "X2_2") (pintype "bidirectional"))
      (node (ref "RTC-CRYSTAL") (pin "P$1") (pinfunction "1_P$1") (pintype "passive"))
    )
    (net (code "52") (name "Net-(RTC-CRYSTAL-2)") (class "Default")
      (node (ref "RTC") (pin "1") (pinfunction "X1_1") (pintype "bidirectional"))
      (node (ref "RTC-CRYSTAL") (pin "P$2") (pinfunction "2_P$2") (pintype "passive"))
    )
    (net (code "53") (name "VCC") (class "Default")
      (node (ref "6V-R1") (pin "2") (pinfunction "2_2") (pintype "passive"))
      (node (ref "B1") (pin "4") (pinfunction "1_4") (pintype "passive"))
      (node (ref "B10") (pin "4") (pinfunction "1_4") (pintype "passive"))
      (node (ref "B11") (pin "4") (pinfunction "1_4") (pintype "passive"))
      (node (ref "B12") (pin "4") (pinfunction "1_4") (pintype "passive"))
      (node (ref "B2") (pin "4") (pinfunction "1_4") (pintype "passive"))
      (node (ref "B3") (pin "4") (pinfunction "1_4") (pintype "passive"))
      (node (ref "B4") (pin "4") (pinfunction "1_4") (pintype "passive"))
      (node (ref "B5") (pin "4") (pinfunction "1_4") (pintype "passive"))
      (node (ref "B6") (pin "4") (pinfunction "1_4") (pintype "passive"))
      (node (ref "B7") (pin "4") (pinfunction "1_4") (pintype "passive"))
      (node (ref "B8") (pin "4") (pinfunction "1_4") (pintype "passive"))
      (node (ref "B9") (pin "4") (pinfunction "1_4") (pintype "passive"))
      (node (ref "GAUGE") (pin "2") (pinfunction "OUT_2") (pintype "output"))
      (node (ref "GAUGE-DCPL") (pin "1") (pinfunction "1_1") (pintype "passive"))
    )
    (net (code "54") (name "unconnected-(ADS1A-D0{slash}CLKOUT-Pad25)") (class "Default")
      (node (ref "ADS1") (pin "25") (pinfunction "D0/CLKOUT_25") (pintype "passive"))
    )
    (net (code "55") (name "unconnected-(ADS1A-D1-Pad26)") (class "Default")
      (node (ref "ADS1") (pin "26") (pinfunction "D1_26") (pintype "passive"))
    )
    (net (code "56") (name "unconnected-(ADS1A-D2-Pad27)") (class "Default")
      (node (ref "ADS1") (pin "27") (pinfunction "D2_27") (pintype "passive"))
    )
    (net (code "57") (name "unconnected-(ADS1A-D3-Pad28)") (class "Default")
      (node (ref "ADS1") (pin "28") (pinfunction "D3_28") (pintype "passive"))
    )
    (net (code "58") (name "unconnected-(ADS2A-D0{slash}CLKOUT-Pad25)") (class "Default")
      (node (ref "ADS2") (pin "25") (pinfunction "D0/CLKOUT_25") (pintype "passive"))
    )
    (net (code "59") (name "unconnected-(ADS2A-D1-Pad26)") (class "Default")
      (node (ref "ADS2") (pin "26") (pinfunction "D1_26") (pintype "passive"))
    )
    (net (code "60") (name "unconnected-(ADS2A-D2-Pad27)") (class "Default")
      (node (ref "ADS2") (pin "27") (pinfunction "D2_27") (pintype "passive"))
    )
    (net (code "61") (name "unconnected-(ADS2A-D3-Pad28)") (class "Default")
      (node (ref "ADS2") (pin "28") (pinfunction "D3_28") (pintype "passive"))
    )
    (net (code "62") (name "unconnected-(ADS3A-D0{slash}CLKOUT-Pad25)") (class "Default")
      (node (ref "ADS3") (pin "25") (pinfunction "D0/CLKOUT_25") (pintype "passive"))
    )
    (net (code "63") (name "unconnected-(ADS3A-D1-Pad26)") (class "Default")
      (node (ref "ADS3") (pin "26") (pinfunction "D1_26") (pintype "passive"))
    )
    (net (code "64") (name "unconnected-(ADS3A-D2-Pad27)") (class "Default")
      (node (ref "ADS3") (pin "27") (pinfunction "D2_27") (pintype "passive"))
    )
    (net (code "65") (name "unconnected-(ADS3A-D3-Pad28)") (class "Default")
      (node (ref "ADS3") (pin "28") (pinfunction "D3_28") (pintype "passive"))
    )
    (net (code "66") (name "unconnected-(MEGA328-ADC7-Pad22)") (class "Default")
      (node (ref "MEGA328") (pin "22") (pinfunction "ADC7_22") (pintype "bidirectional"))
    )
    (net (code "67") (name "unconnected-(MEGA328-PC0(ADC0)-Pad23)") (class "Default")
      (node (ref "MEGA328") (pin "23") (pinfunction "PC0(ADC0)_23") (pintype "bidirectional"))
    )
    (net (code "68") (name "unconnected-(MEGA328-PC1(ADC1)-Pad24)") (class "Default")
      (node (ref "MEGA328") (pin "24") (pinfunction "PC1(ADC1)_24") (pintype "bidirectional"))
    )
    (net (code "69") (name "unconnected-(MEGA328-PC2(ADC2)-Pad25)") (class "Default")
      (node (ref "MEGA328") (pin "25") (pinfunction "PC2(ADC2)_25") (pintype "bidirectional"))
    )
    (net (code "70") (name "unconnected-(MEGA328-PC3(ADC3)-Pad26)") (class "Default")
      (node (ref "MEGA328") (pin "26") (pinfunction "PC3(ADC3)_26") (pintype "bidirectional"))
    )
    (net (code "71") (name "unconnected-(MEGA328-PD0(RXD)-Pad30)") (class "Default")
      (node (ref "MEGA328") (pin "30") (pinfunction "PD0(RXD)_30") (pintype "bidirectional"))
    )
    (net (code "72") (name "unconnected-(MEGA328-PD1(TXD)-Pad31)") (class "Default")
      (node (ref "MEGA328") (pin "31") (pinfunction "PD1(TXD)_31") (pintype "bidirectional"))
    )
    (net (code "73") (name "unconnected-(MEGA328-PD2(INT0)-Pad32)") (class "Default")
      (node (ref "MEGA328") (pin "32") (pinfunction "PD2(INT0)_32") (pintype "bidirectional"))
    )
    (net (code "74") (name "unconnected-(SD-RSV-PadRSV1)") (class "Default")
      (node (ref "SD") (pin "RSV1") (pinfunction "RSV_RSV1") (pintype "bidirectional"))
    )
    (net (code "75") (name "unconnected-(SD-RSV-PadRSV2)") (class "Default")
      (node (ref "SD") (pin "RSV2") (pinfunction "RSV_RSV2") (pintype "bidirectional"))
    )
  )
)
